# Shift_Voltage_with_IN-OUT.net
KiCad netlist of a schematic drawn in Altium Designer
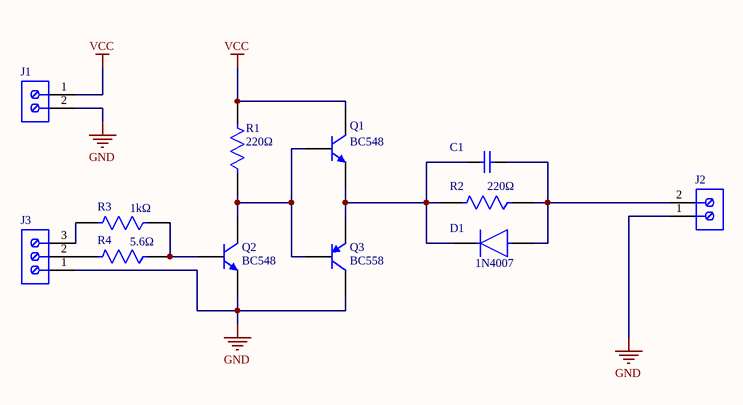
[diagram p0: Shift Voltage with IN-OUT.SchDoc]

(export (version "E")
  (design (tool "Eeschema 10.0.6"))
  (components
    (comp (ref "C1")
      (value "C0402C104K4RACTU")
      (footprint "CAPC1005X55X30LL05T10")
      (fields (field (name "MANUFACTURER") "Kemet"))
      (libsource (lib "Altium Content Vault") (part "CAP"))
    )
    (comp (ref "D1")
      (value "1N4007")
      (footprint "FP-1N4007-TP-MFG")
      (description "DIODE GEN PURP 1KV 1A DO41")
      (libsource (lib "Altium Content Vault") (part "d7152d700b627762746794eb795d46e"))
    )
    (comp (ref "J1")
      (value "1725656")
      (footprint "PHOE-1725656-2")
      (description "Male Header, Pitch 2.54 mm, 1 x 2 Position, Height 9 mm, Tail Length 3.5 mm")
      (fields (field (name "MANUFACTURER") "Phoenix Contact"))
      (libsource (lib "Altium Content Vault") (part "CN-1P-F-TB2"))
    )
    (comp (ref "J2")
      (value "1725656")
      (footprint "PHOE-1725656-2")
      (description "Male Header, Pitch 2.54 mm, 1 x 2 Position, Height 9 mm, Tail Length 3.5 mm")
      (fields (field (name "MANUFACTURER") "Phoenix Contact"))
      (libsource (lib "Altium Content Vault") (part "CN-1P-F-TB2"))
    )
    (comp (ref "J3")
      (value "691214110003")
      (footprint "691214110003")
      (fields (field (name "VOLTAGE") "300V"))
      (libsource (lib "Altium Content Vault") (part "TBL - 1R - 03P - Screw"))
    )
    (comp (ref "Q1")
      (value "BC548")
      (footprint "ONSC-TO-92-3-29-11_AM_BL")
      (description "Amplifier Transistor, NPN Silicon, 3-Pin TO-92, Pb-Free, Tape and Reel")
      (fields (field (name "MANUFACTURER") "On Semiconductor") (field (name "PARTNUMBER") "BC548BRL1G"))
      (libsource (lib "Altium Content Vault") (part "ONSC-NPN-C1B2E3-3"))
    )
    (comp (ref "Q2")
      (value "BC548")
      (footprint "ONSC-TO-92-3-29-11_AM_BL")
      (description "Amplifier Transistor, NPN Silicon, 3-Pin TO-92, Pb-Free, Tape and Reel")
      (fields (field (name "MANUFACTURER") "On Semiconductor") (field (name "PARTNUMBER") "BC548BRL1G"))
      (libsource (lib "Altium Content Vault") (part "ONSC-NPN-C1B2E3-3"))
    )
    (comp (ref "Q3")
      (value "BC558")
      (footprint "ONSC-TO-92-3-29-11_AM_BL")
      (description "Amplifier Transistor, PNP Silicon, 3-Pin TO-92, Pb-Free, Tape and Reel")
      (fields (field (name "MANUFACTURER") "On Semiconductor") (field (name "PARTNUMBER") "BC558BRL1G"))
      (libsource (lib "Altium Content Vault") (part "ONSC-PNP-C1B2E3-3"))
    )
    (comp (ref "R1")
      (value "220Ω")
      (footprint "FP-CF14-MFG")
      (description "RES 7.5K OHM 1/4W 5% AXIAL")
      (fields (field (name "TOLERANCE") "5%"))
      (libsource (lib "Altium Content Vault") (part "1029c3af85768c4190bb7ad29bc67b5"))
    )
    (comp (ref "R2")
      (value "220Ω")
      (footprint "FP-CF14-MFG")
      (description "RES 7.5K OHM 1/4W 5% AXIAL")
      (fields (field (name "TOLERANCE") "5%"))
      (libsource (lib "Altium Content Vault") (part "1029c3af85768c4190bb7ad29bc67b5"))
    )
    (comp (ref "R3")
      (value "1kΩ")
      (footprint "FP-CF14-MFG")
      (description "RES 7.5K OHM 1/4W 5% AXIAL")
      (fields (field (name "TOLERANCE") "5%"))
      (libsource (lib "Altium Content Vault") (part "1029c3af85768c4190bb7ad29bc67b5"))
    )
    (comp (ref "R4")
      (value "5.6Ω")
      (footprint "FP-CF14-MFG")
      (description "RES 7.5K OHM 1/4W 5% AXIAL")
      (fields (field (name "TOLERANCE") "5%"))
      (libsource (lib "Altium Content Vault") (part "1029c3af85768c4190bb7ad29bc67b5"))
    )
  )
  (nets
    (net (code "1") (name "GND") (class "Default")
      (node (ref "J1") (pin "2") (pinfunction "2_2") (pintype "passive"))
      (node (ref "J2") (pin "1") (pinfunction "1_1") (pintype "passive"))
      (node (ref "J3") (pin "1") (pinfunction "1_1") (pintype "passive"))
      (node (ref "Q2") (pin "3") (pinfunction "E_3") (pintype "passive"))
      (node (ref "Q3") (pin "1") (pinfunction "C_1") (pintype "passive"))
    )
    (net (code "2") (name "Net-(D1-A)") (class "Default")
      (node (ref "C1") (pin "2") (pinfunction "2_2") (pintype "passive"))
      (node (ref "D1") (pin "2") (pinfunction "A_2") (pintype "passive"))
      (node (ref "J2") (pin "2") (pinfunction "2_2") (pintype "passive"))
      (node (ref "R2") (pin "1") (pinfunction "1_1") (pintype "passive"))
    )
    (net (code "3") (name "Net-(D1-C)") (class "Default")
      (node (ref "C1") (pin "1") (pinfunction "1_1") (pintype "passive"))
      (node (ref "D1") (pin "1") (pinfunction "C_1") (pintype "passive"))
      (node (ref "Q1") (pin "3") (pinfunction "E_3") (pintype "passive"))
      (node (ref "Q3") (pin "3") (pinfunction "E_3") (pintype "passive"))
      (node (ref "R2") (pin "2") (pinfunction "2_2") (pintype "passive"))
    )
    (net (code "4") (name "Net-(J3-Pad2)") (class "Default")
      (node (ref "J3") (pin "2") (pinfunction "2_2") (pintype "passive"))
      (node (ref "R4") (pin "2") (pinfunction "2_2") (pintype "passive"))
    )
    (net (code "5") (name "Net-(J3-Pad3)") (class "Default")
      (node (ref "J3") (pin "3") (pinfunction "3_3") (pintype "passive"))
      (node (ref "R3") (pin "2") (pinfunction "2_2") (pintype "passive"))
    )
    (net (code "6") (name "Net-(Q1-B)") (class "Default")
      (node (ref "Q1") (pin "2") (pinfunction "B_2") (pintype "passive"))
      (node (ref "Q2") (pin "1") (pinfunction "C_1") (pintype "passive"))
      (node (ref "Q3") (pin "2") (pinfunction "B_2") (pintype "passive"))
      (node (ref "R1") (pin "1") (pinfunction "1_1") (pintype "passive"))
    )
    (net (code "7") (name "Net-(Q2-B)") (class "Default")
      (node (ref "Q2") (pin "2") (pinfunction "B_2") (pintype "passive"))
      (node (ref "R3") (pin "1") (pinfunction "1_1") (pintype "passive"))
      (node (ref "R4") (pin "1") (pinfunction "1_1") (pintype "passive"))
    )
    (net (code "8") (name "VCC") (class "Default")
      (node (ref "J1") (pin "1") (pinfunction "1_1") (pintype "passive"))
      (node (ref "Q1") (pin "1") (pinfunction "C_1") (pintype "passive"))
      (node (ref "R1") (pin "2") (pinfunction "2_2") (pintype "passive"))
    )
  )
)
